# Hallsonde.net
KiCad netlist of a schematic drawn in EAGLE
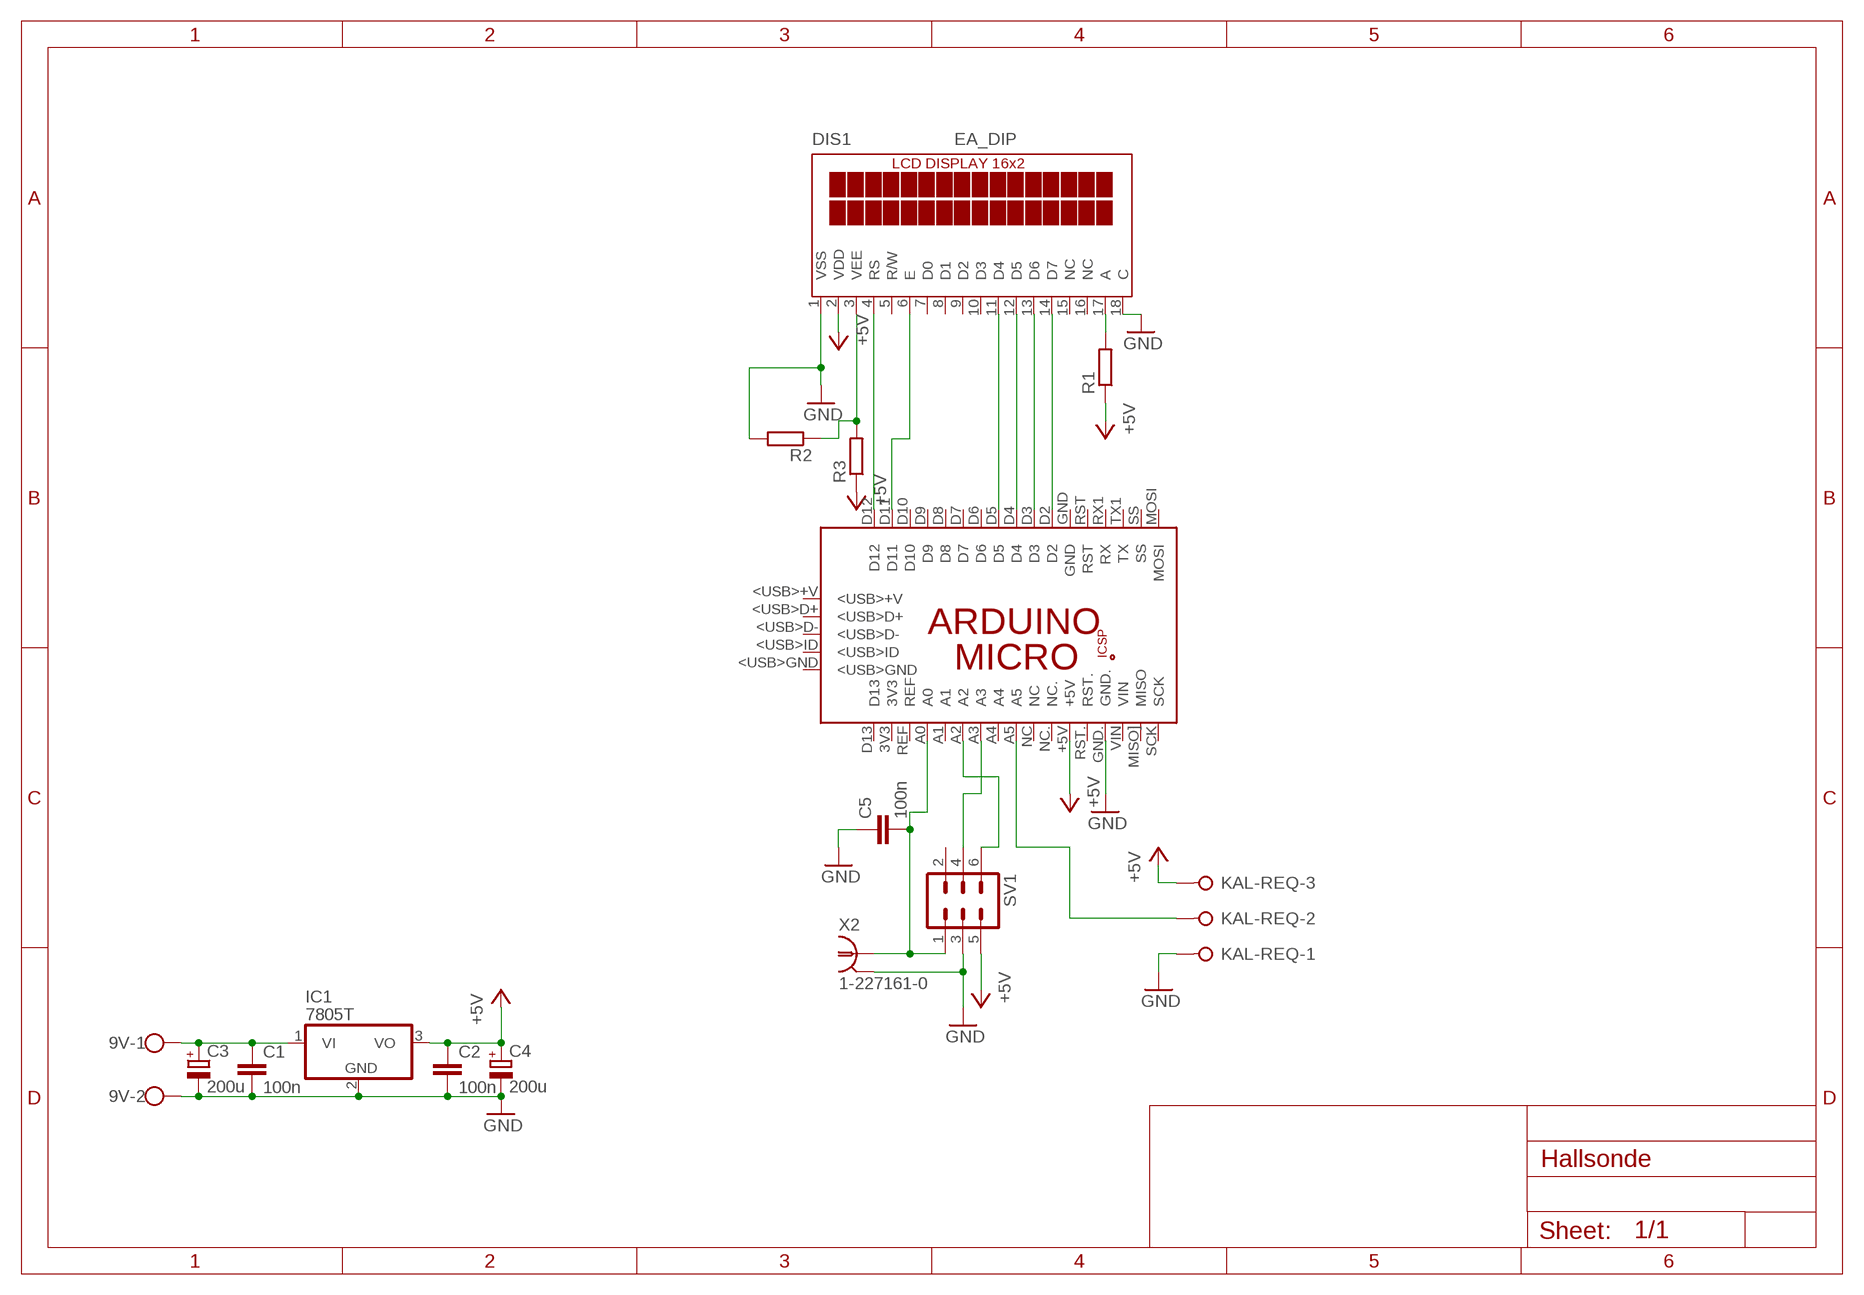
[diagram p0: schematic, sheet 1]

(export (version "E")
  (design (tool "Eeschema 10.0.6"))
  (components
    (comp (ref "9V")
      (value "W237-102")
      (footprint "eagle-import:W237-102")
      (fields (field (name "MPN") "237-102"))
      (libsource (lib "eagle-import") (part "W237-102"))
    )
    (comp (ref "C1")
      (value "100n")
      (footprint "eagle-import:C0805")
      (libsource (lib "eagle-import") (part "C-EUC0805"))
    )
    (comp (ref "C2")
      (value "100n")
      (footprint "eagle-import:C0805")
      (libsource (lib "eagle-import") (part "C-EUC0805"))
    )
    (comp (ref "C3")
      (value "200u")
      (footprint "eagle-import:E2,5-6E")
      (libsource (lib "eagle-import") (part "CPOL-EUE2,5-6E"))
    )
    (comp (ref "C4")
      (value "200u")
      (footprint "eagle-import:E2,5-6E")
      (libsource (lib "eagle-import") (part "CPOL-EUE2,5-6E"))
    )
    (comp (ref "C5")
      (value "100n")
      (footprint "eagle-import:C0805")
      (libsource (lib "eagle-import") (part "C-EUC0805"))
    )
    (comp (ref "DIS1")
      (value "EA_DIP")
      (footprint "eagle-import:EA_DIP")
      (libsource (lib "eagle-import") (part "EA_DIP"))
    )
    (comp (ref "IC1")
      (value "7805T")
      (footprint "eagle-import:TO220H")
      (libsource (lib "eagle-import") (part "78T05"))
    )
    (comp (ref "KAL-REQ")
      (value "W237-3E")
      (footprint "eagle-import:W237-3E")
      (libsource (lib "eagle-import") (part "W237-3E"))
    )
    (comp (ref "PCB1")
      (value "ARDUINO_MICRO")
      (footprint "eagle-import:ARDUINO_MICRO")
      (libsource (lib "eagle-import") (part "ARDUINO_MICRO"))
    )
    (comp (ref "R1")
      (value "R-EU_M0805")
      (footprint "eagle-import:M0805")
      (libsource (lib "eagle-import") (part "R-EU_M0805"))
    )
    (comp (ref "R2")
      (value "R-EU_M0805")
      (footprint "eagle-import:M0805")
      (libsource (lib "eagle-import") (part "R-EU_M0805"))
    )
    (comp (ref "R3")
      (value "R-EU_M0805")
      (footprint "eagle-import:M0805")
      (libsource (lib "eagle-import") (part "R-EU_M0805"))
    )
    (comp (ref "SV1")
      (value "ML6L")
      (footprint "eagle-import:ML6L")
      (libsource (lib "eagle-import") (part "ML6L"))
    )
    (comp (ref "X2")
      (value "1-227161-0")
      (footprint "eagle-import:AMP_227161")
      (fields (field (name "MF") "TYCO ELECTRONICS") (field (name "MPN") "1-227161"))
      (libsource (lib "eagle-import") (part "?2271611--0"))
    )
  )
  (nets
    (net (code "1") (name "+5V") (class "Default")
      (node (ref "C2") (pin "1") (pinfunction "1_1") (pintype "passive"))
      (node (ref "C4") (pin "+") (pinfunction "+_+") (pintype "passive"))
      (node (ref "DIS1") (pin "2") (pinfunction "VDD_2") (pintype "power_in"))
      (node (ref "IC1") (pin "3") (pinfunction "VO_3") (pintype "passive"))
      (node (ref "KAL-REQ") (pin "3") (pinfunction "KL_3") (pintype "passive"))
      (node (ref "PCB1") (pin "+5V") (pinfunction "+5V_+5V") (pintype "bidirectional"))
      (node (ref "R1") (pin "1") (pinfunction "1_1") (pintype "passive"))
      (node (ref "R3") (pin "1") (pinfunction "1_1") (pintype "passive"))
      (node (ref "SV1") (pin "5") (pinfunction "5_5") (pintype "passive"))
    )
    (net (code "2") (name "GND") (class "Default")
      (node (ref "9V") (pin "2") (pinfunction "KL_2") (pintype "passive"))
      (node (ref "C1") (pin "2") (pinfunction "2_2") (pintype "passive"))
      (node (ref "C2") (pin "2") (pinfunction "2_2") (pintype "passive"))
      (node (ref "C3") (pin "-") (pinfunction "-_-") (pintype "passive"))
      (node (ref "C4") (pin "-") (pinfunction "-_-") (pintype "passive"))
      (node (ref "C5") (pin "1") (pinfunction "1_1") (pintype "passive"))
      (node (ref "DIS1") (pin "1") (pinfunction "VSS_1") (pintype "power_in"))
      (node (ref "DIS1") (pin "18") (pinfunction "C_18") (pintype "passive"))
      (node (ref "IC1") (pin "2") (pinfunction "GND_2") (pintype "passive"))
      (node (ref "KAL-REQ") (pin "1") (pinfunction "KL_1") (pintype "passive"))
      (node (ref "PCB1") (pin "GND.") (pinfunction "GND._GND.") (pintype "bidirectional"))
      (node (ref "R2") (pin "2") (pinfunction "2_2") (pintype "passive"))
      (node (ref "SV1") (pin "3") (pinfunction "3_3") (pintype "passive"))
      (node (ref "X2") (pin "2") (pinfunction "2_2") (pintype "passive"))
    )
    (net (code "3") (name "Net-(9VA-KL)") (class "Default")
      (node (ref "9V") (pin "1") (pinfunction "KL_1") (pintype "passive"))
      (node (ref "C1") (pin "1") (pinfunction "1_1") (pintype "passive"))
      (node (ref "C3") (pin "+") (pinfunction "+_+") (pintype "passive"))
      (node (ref "IC1") (pin "1") (pinfunction "VI_1") (pintype "input"))
    )
    (net (code "4") (name "Net-(C5-Pad2)") (class "Default")
      (node (ref "C5") (pin "2") (pinfunction "2_2") (pintype "passive"))
      (node (ref "PCB1") (pin "A0") (pinfunction "A0_A0") (pintype "bidirectional"))
      (node (ref "SV1") (pin "1") (pinfunction "1_1") (pintype "passive"))
      (node (ref "X2") (pin "1") (pinfunction "1_1") (pintype "passive"))
    )
    (net (code "5") (name "Net-(DIS1-A)") (class "Default")
      (node (ref "DIS1") (pin "17") (pinfunction "A_17") (pintype "passive"))
      (node (ref "R1") (pin "2") (pinfunction "2_2") (pintype "passive"))
    )
    (net (code "6") (name "Net-(DIS1-D4)") (class "Default")
      (node (ref "DIS1") (pin "11") (pinfunction "D4_11") (pintype "input"))
      (node (ref "PCB1") (pin "D5") (pinfunction "D5_D5") (pintype "bidirectional"))
    )
    (net (code "7") (name "Net-(DIS1-D5)") (class "Default")
      (node (ref "DIS1") (pin "12") (pinfunction "D5_12") (pintype "input"))
      (node (ref "PCB1") (pin "D4") (pinfunction "D4_D4") (pintype "bidirectional"))
    )
    (net (code "8") (name "Net-(DIS1-D6)") (class "Default")
      (node (ref "DIS1") (pin "13") (pinfunction "D6_13") (pintype "input"))
      (node (ref "PCB1") (pin "D3") (pinfunction "D3_D3") (pintype "bidirectional"))
    )
    (net (code "9") (name "Net-(DIS1-D7)") (class "Default")
      (node (ref "DIS1") (pin "14") (pinfunction "D7_14") (pintype "input"))
      (node (ref "PCB1") (pin "D2") (pinfunction "D2_D2") (pintype "bidirectional"))
    )
    (net (code "10") (name "Net-(DIS1-E)") (class "Default")
      (node (ref "DIS1") (pin "6") (pinfunction "E_6") (pintype "input"))
      (node (ref "PCB1") (pin "D11") (pinfunction "D11_D11") (pintype "bidirectional"))
    )
    (net (code "11") (name "Net-(DIS1-RS)") (class "Default")
      (node (ref "DIS1") (pin "4") (pinfunction "RS_4") (pintype "input"))
      (node (ref "PCB1") (pin "D12") (pinfunction "D12_D12") (pintype "bidirectional"))
    )
    (net (code "12") (name "Net-(DIS1-VEE)") (class "Default")
      (node (ref "DIS1") (pin "3") (pinfunction "VEE_3") (pintype "power_in"))
      (node (ref "R2") (pin "1") (pinfunction "1_1") (pintype "passive"))
      (node (ref "R3") (pin "2") (pinfunction "2_2") (pintype "passive"))
    )
    (net (code "13") (name "Net-(KAL-REQB-KL)") (class "Default")
      (node (ref "KAL-REQ") (pin "2") (pinfunction "KL_2") (pintype "passive"))
      (node (ref "PCB1") (pin "A5") (pinfunction "A5_A5") (pintype "bidirectional"))
    )
    (net (code "14") (name "Net-(PCB1-PadA2)") (class "Default")
      (node (ref "PCB1") (pin "A2") (pinfunction "A2_A2") (pintype "bidirectional"))
      (node (ref "SV1") (pin "6") (pinfunction "6_6") (pintype "passive"))
    )
    (net (code "15") (name "Net-(PCB1-PadA3)") (class "Default")
      (node (ref "PCB1") (pin "A3") (pinfunction "A3_A3") (pintype "bidirectional"))
      (node (ref "SV1") (pin "4") (pinfunction "4_4") (pintype "passive"))
    )
    (net (code "16") (name "unconnected-(DIS1-D0-Pad7)") (class "Default")
      (node (ref "DIS1") (pin "7") (pinfunction "D0_7") (pintype "input"))
    )
    (net (code "17") (name "unconnected-(DIS1-D1-Pad8)") (class "Default")
      (node (ref "DIS1") (pin "8") (pinfunction "D1_8") (pintype "input"))
    )
    (net (code "18") (name "unconnected-(DIS1-D2-Pad9)") (class "Default")
      (node (ref "DIS1") (pin "9") (pinfunction "D2_9") (pintype "input"))
    )
    (net (code "19") (name "unconnected-(DIS1-D3-Pad10)") (class "Default")
      (node (ref "DIS1") (pin "10") (pinfunction "D3_10") (pintype "input"))
    )
    (net (code "20") (name "unconnected-(DIS1-NC-Pad15)") (class "Default")
      (node (ref "DIS1") (pin "15") (pinfunction "NC_15") (pintype "no_connect"))
    )
    (net (code "21") (name "unconnected-(DIS1-NC-Pad16)") (class "Default")
      (node (ref "DIS1") (pin "16") (pinfunction "NC_16") (pintype "no_connect"))
    )
    (net (code "22") (name "unconnected-(DIS1-R{slash}W-Pad5)") (class "Default")
      (node (ref "DIS1") (pin "5") (pinfunction "R/W_5") (pintype "input"))
    )
    (net (code "23") (name "unconnected-(PCB1-MISO-PadMISO])") (class "Default")
      (node (ref "PCB1") (pin "MISO]") (pinfunction "MISO_MISO]") (pintype "bidirectional"))
    )
    (net (code "24") (name "unconnected-(PCB1-Pad3V3)") (class "Default")
      (node (ref "PCB1") (pin "3V3") (pinfunction "3V3_3V3") (pintype "bidirectional"))
    )
    (net (code "25") (name "unconnected-(PCB1-Pad5V)") (class "Default")
      (node (ref "PCB1") (pin "5V") (pinfunction "5V_5V") (pintype "bidirectional"))
    )
    (net (code "26") (name "unconnected-(PCB1-Pad<USB>+V)") (class "Default")
      (node (ref "PCB1") (pin "<USB>+V") (pinfunction "<USB>+V_<USB>+V") (pintype "bidirectional"))
    )
    (net (code "27") (name "unconnected-(PCB1-Pad<USB>D+)") (class "Default")
      (node (ref "PCB1") (pin "<USB>D+") (pinfunction "<USB>D+_<USB>D+") (pintype "bidirectional"))
    )
    (net (code "28") (name "unconnected-(PCB1-Pad<USB>D-)") (class "Default")
      (node (ref "PCB1") (pin "<USB>D-") (pinfunction "<USB>D-_<USB>D-") (pintype "bidirectional"))
    )
    (net (code "29") (name "unconnected-(PCB1-Pad<USB>GND)") (class "Default")
      (node (ref "PCB1") (pin "<USB>GND") (pinfunction "<USB>GND_<USB>GND") (pintype "bidirectional"))
    )
    (net (code "30") (name "unconnected-(PCB1-Pad<USB>ID)") (class "Default")
      (node (ref "PCB1") (pin "<USB>ID") (pinfunction "<USB>ID_<USB>ID") (pintype "bidirectional"))
    )
    (net (code "31") (name "unconnected-(PCB1-PadA1)") (class "Default")
      (node (ref "PCB1") (pin "A1") (pinfunction "A1_A1") (pintype "bidirectional"))
    )
    (net (code "32") (name "unconnected-(PCB1-PadA4)") (class "Default")
      (node (ref "PCB1") (pin "A4") (pinfunction "A4_A4") (pintype "bidirectional"))
    )
    (net (code "33") (name "unconnected-(PCB1-PadD6)") (class "Default")
      (node (ref "PCB1") (pin "D6") (pinfunction "D6_D6") (pintype "bidirectional"))
    )
    (net (code "34") (name "unconnected-(PCB1-PadD7)") (class "Default")
      (node (ref "PCB1") (pin "D7") (pinfunction "D7_D7") (pintype "bidirectional"))
    )
    (net (code "35") (name "unconnected-(PCB1-PadD8)") (class "Default")
      (node (ref "PCB1") (pin "D8") (pinfunction "D8_D8") (pintype "bidirectional"))
    )
    (net (code "36") (name "unconnected-(PCB1-PadD9)") (class "Default")
      (node (ref "PCB1") (pin "D9") (pinfunction "D9_D9") (pintype "bidirectional"))
    )
    (net (code "37") (name "unconnected-(PCB1-PadD10)") (class "Default")
      (node (ref "PCB1") (pin "D10") (pinfunction "D10_D10") (pintype "bidirectional"))
    )
    (net (code "38") (name "unconnected-(PCB1-PadD13)") (class "Default")
      (node (ref "PCB1") (pin "D13") (pinfunction "D13_D13") (pintype "bidirectional"))
    )
    (net (code "39") (name "unconnected-(PCB1-PadGND)") (class "Default")
      (node (ref "PCB1") (pin "GND") (pinfunction "GND_GND") (pintype "bidirectional"))
    )
    (net (code "40") (name "unconnected-(PCB1-PadGND_)") (class "Default")
      (node (ref "PCB1") (pin "GND_") (pinfunction "GND__GND_") (pintype "bidirectional"))
    )
    (net (code "41") (name "unconnected-(PCB1-PadMISO.)") (class "Default")
      (node (ref "PCB1") (pin "MISO.") (pinfunction "MISO._MISO.") (pintype "bidirectional"))
    )
    (net (code "42") (name "unconnected-(PCB1-PadMOSI)") (class "Default")
      (node (ref "PCB1") (pin "MOSI") (pinfunction "MOSI_MOSI") (pintype "bidirectional"))
    )
    (net (code "43") (name "unconnected-(PCB1-PadMOSI.)") (class "Default")
      (node (ref "PCB1") (pin "MOSI.") (pinfunction "MOSI._MOSI.") (pintype "bidirectional"))
    )
    (net (code "44") (name "unconnected-(PCB1-PadNC)") (class "Default")
      (node (ref "PCB1") (pin "NC") (pinfunction "NC_NC") (pintype "bidirectional"))
    )
    (net (code "45") (name "unconnected-(PCB1-PadNC.)") (class "Default")
      (node (ref "PCB1") (pin "NC.") (pinfunction "NC._NC.") (pintype "bidirectional"))
    )
    (net (code "46") (name "unconnected-(PCB1-PadREF)") (class "Default")
      (node (ref "PCB1") (pin "REF") (pinfunction "REF_REF") (pintype "bidirectional"))
    )
    (net (code "47") (name "unconnected-(PCB1-PadRESET..)") (class "Default")
      (node (ref "PCB1") (pin "RESET..") (pinfunction "RESET.._RESET..") (pintype "bidirectional"))
    )
    (net (code "48") (name "unconnected-(PCB1-PadRST)") (class "Default")
      (node (ref "PCB1") (pin "RST") (pinfunction "RST_RST") (pintype "bidirectional"))
    )
    (net (code "49") (name "unconnected-(PCB1-PadRST.)") (class "Default")
      (node (ref "PCB1") (pin "RST.") (pinfunction "RST._RST.") (pintype "bidirectional"))
    )
    (net (code "50") (name "unconnected-(PCB1-PadSCK)") (class "Default")
      (node (ref "PCB1") (pin "SCK") (pinfunction "SCK_SCK") (pintype "bidirectional"))
    )
    (net (code "51") (name "unconnected-(PCB1-PadSCK.)") (class "Default")
      (node (ref "PCB1") (pin "SCK.") (pinfunction "SCK._SCK.") (pintype "bidirectional"))
    )
    (net (code "52") (name "unconnected-(PCB1-PadSS)") (class "Default")
      (node (ref "PCB1") (pin "SS") (pinfunction "SS_SS") (pintype "bidirectional"))
    )
    (net (code "53") (name "unconnected-(PCB1-PadVIN)") (class "Default")
      (node (ref "PCB1") (pin "VIN") (pinfunction "VIN_VIN") (pintype "bidirectional"))
    )
    (net (code "54") (name "unconnected-(PCB1-RX-PadRX1)") (class "Default")
      (node (ref "PCB1") (pin "RX1") (pinfunction "RX_RX1") (pintype "bidirectional"))
    )
    (net (code "55") (name "unconnected-(PCB1-TX-PadTX1)") (class "Default")
      (node (ref "PCB1") (pin "TX1") (pinfunction "TX_TX1") (pintype "bidirectional"))
    )
    (net (code "56") (name "unconnected-(SV1-Pad2)") (class "Default")
      (node (ref "SV1") (pin "2") (pinfunction "2_2") (pintype "passive"))
    )
  )
)
